# NinjaLantern-171001.net
KiCad netlist of a schematic drawn in EAGLE
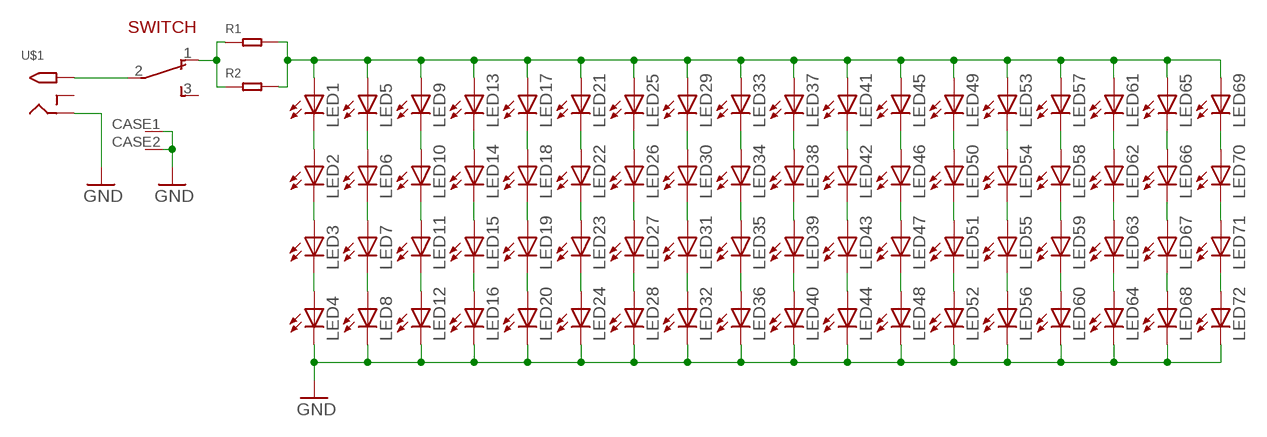
[diagram p0: schematic, sheet 1]

(export (version "E")
  (design (tool "Eeschema 10.0.6"))
  (components
    (comp (ref "LED1")
      (value "LED5MM")
      (footprint "eagle-import:LED5MM")
      (libsource (lib "eagle-import") (part "LED5MM"))
    )
    (comp (ref "LED2")
      (value "LED5MM")
      (footprint "eagle-import:LED5MM")
      (libsource (lib "eagle-import") (part "LED5MM"))
    )
    (comp (ref "LED3")
      (value "LED5MM")
      (footprint "eagle-import:LED5MM")
      (libsource (lib "eagle-import") (part "LED5MM"))
    )
    (comp (ref "LED4")
      (value "LED5MM")
      (footprint "eagle-import:LED5MM")
      (libsource (lib "eagle-import") (part "LED5MM"))
    )
    (comp (ref "LED5")
      (value "LED5MM")
      (footprint "eagle-import:LED5MM")
      (libsource (lib "eagle-import") (part "LED5MM"))
    )
    (comp (ref "LED6")
      (value "LED5MM")
      (footprint "eagle-import:LED5MM")
      (libsource (lib "eagle-import") (part "LED5MM"))
    )
    (comp (ref "LED7")
      (value "LED5MM")
      (footprint "eagle-import:LED5MM")
      (libsource (lib "eagle-import") (part "LED5MM"))
    )
    (comp (ref "LED8")
      (value "LED5MM")
      (footprint "eagle-import:LED5MM")
      (libsource (lib "eagle-import") (part "LED5MM"))
    )
    (comp (ref "LED9")
      (value "LED5MM")
      (footprint "eagle-import:LED5MM")
      (libsource (lib "eagle-import") (part "LED5MM"))
    )
    (comp (ref "LED10")
      (value "LED5MM")
      (footprint "eagle-import:LED5MM")
      (libsource (lib "eagle-import") (part "LED5MM"))
    )
    (comp (ref "LED11")
      (value "LED5MM")
      (footprint "eagle-import:LED5MM")
      (libsource (lib "eagle-import") (part "LED5MM"))
    )
    (comp (ref "LED12")
      (value "LED5MM")
      (footprint "eagle-import:LED5MM")
      (libsource (lib "eagle-import") (part "LED5MM"))
    )
    (comp (ref "LED13")
      (value "LED5MM")
      (footprint "eagle-import:LED5MM")
      (libsource (lib "eagle-import") (part "LED5MM"))
    )
    (comp (ref "LED14")
      (value "LED5MM")
      (footprint "eagle-import:LED5MM")
      (libsource (lib "eagle-import") (part "LED5MM"))
    )
    (comp (ref "LED15")
      (value "LED5MM")
      (footprint "eagle-import:LED5MM")
      (libsource (lib "eagle-import") (part "LED5MM"))
    )
    (comp (ref "LED16")
      (value "LED5MM")
      (footprint "eagle-import:LED5MM")
      (libsource (lib "eagle-import") (part "LED5MM"))
    )
    (comp (ref "LED17")
      (value "LED5MM")
      (footprint "eagle-import:LED5MM")
      (libsource (lib "eagle-import") (part "LED5MM"))
    )
    (comp (ref "LED18")
      (value "LED5MM")
      (footprint "eagle-import:LED5MM")
      (libsource (lib "eagle-import") (part "LED5MM"))
    )
    (comp (ref "LED19")
      (value "LED5MM")
      (footprint "eagle-import:LED5MM")
      (libsource (lib "eagle-import") (part "LED5MM"))
    )
    (comp (ref "LED20")
      (value "LED5MM")
      (footprint "eagle-import:LED5MM")
      (libsource (lib "eagle-import") (part "LED5MM"))
    )
    (comp (ref "LED21")
      (value "LED5MM")
      (footprint "eagle-import:LED5MM")
      (libsource (lib "eagle-import") (part "LED5MM"))
    )
    (comp (ref "LED22")
      (value "LED5MM")
      (footprint "eagle-import:LED5MM")
      (libsource (lib "eagle-import") (part "LED5MM"))
    )
    (comp (ref "LED23")
      (value "LED5MM")
      (footprint "eagle-import:LED5MM")
      (libsource (lib "eagle-import") (part "LED5MM"))
    )
    (comp (ref "LED24")
      (value "LED5MM")
      (footprint "eagle-import:LED5MM")
      (libsource (lib "eagle-import") (part "LED5MM"))
    )
    (comp (ref "LED25")
      (value "LED5MM")
      (footprint "eagle-import:LED5MM")
      (libsource (lib "eagle-import") (part "LED5MM"))
    )
    (comp (ref "LED26")
      (value "LED5MM")
      (footprint "eagle-import:LED5MM")
      (libsource (lib "eagle-import") (part "LED5MM"))
    )
    (comp (ref "LED27")
      (value "LED5MM")
      (footprint "eagle-import:LED5MM")
      (libsource (lib "eagle-import") (part "LED5MM"))
    )
    (comp (ref "LED28")
      (value "LED5MM")
      (footprint "eagle-import:LED5MM")
      (libsource (lib "eagle-import") (part "LED5MM"))
    )
    (comp (ref "LED29")
      (value "LED5MM")
      (footprint "eagle-import:LED5MM")
      (libsource (lib "eagle-import") (part "LED5MM"))
    )
    (comp (ref "LED30")
      (value "LED5MM")
      (footprint "eagle-import:LED5MM")
      (libsource (lib "eagle-import") (part "LED5MM"))
    )
    (comp (ref "LED31")
      (value "LED5MM")
      (footprint "eagle-import:LED5MM")
      (libsource (lib "eagle-import") (part "LED5MM"))
    )
    (comp (ref "LED32")
      (value "LED5MM")
      (footprint "eagle-import:LED5MM")
      (libsource (lib "eagle-import") (part "LED5MM"))
    )
    (comp (ref "LED33")
      (value "LED5MM")
      (footprint "eagle-import:LED5MM")
      (libsource (lib "eagle-import") (part "LED5MM"))
    )
    (comp (ref "LED34")
      (value "LED5MM")
      (footprint "eagle-import:LED5MM")
      (libsource (lib "eagle-import") (part "LED5MM"))
    )
    (comp (ref "LED35")
      (value "LED5MM")
      (footprint "eagle-import:LED5MM")
      (libsource (lib "eagle-import") (part "LED5MM"))
    )
    (comp (ref "LED36")
      (value "LED5MM")
      (footprint "eagle-import:LED5MM")
      (libsource (lib "eagle-import") (part "LED5MM"))
    )
    (comp (ref "LED37")
      (value "LED5MM")
      (footprint "eagle-import:LED5MM")
      (libsource (lib "eagle-import") (part "LED5MM"))
    )
    (comp (ref "LED38")
      (value "LED5MM")
      (footprint "eagle-import:LED5MM")
      (libsource (lib "eagle-import") (part "LED5MM"))
    )
    (comp (ref "LED39")
      (value "LED5MM")
      (footprint "eagle-import:LED5MM")
      (libsource (lib "eagle-import") (part "LED5MM"))
    )
    (comp (ref "LED40")
      (value "LED5MM")
      (footprint "eagle-import:LED5MM")
      (libsource (lib "eagle-import") (part "LED5MM"))
    )
    (comp (ref "LED41")
      (value "LED5MM")
      (footprint "eagle-import:LED5MM")
      (libsource (lib "eagle-import") (part "LED5MM"))
    )
    (comp (ref "LED42")
      (value "LED5MM")
      (footprint "eagle-import:LED5MM")
      (libsource (lib "eagle-import") (part "LED5MM"))
    )
    (comp (ref "LED43")
      (value "LED5MM")
      (footprint "eagle-import:LED5MM")
      (libsource (lib "eagle-import") (part "LED5MM"))
    )
    (comp (ref "LED44")
      (value "LED5MM")
      (footprint "eagle-import:LED5MM")
      (libsource (lib "eagle-import") (part "LED5MM"))
    )
    (comp (ref "LED45")
      (value "LED5MM")
      (footprint "eagle-import:LED5MM")
      (libsource (lib "eagle-import") (part "LED5MM"))
    )
    (comp (ref "LED46")
      (value "LED5MM")
      (footprint "eagle-import:LED5MM")
      (libsource (lib "eagle-import") (part "LED5MM"))
    )
    (comp (ref "LED47")
      (value "LED5MM")
      (footprint "eagle-import:LED5MM")
      (libsource (lib "eagle-import") (part "LED5MM"))
    )
    (comp (ref "LED48")
      (value "LED5MM")
      (footprint "eagle-import:LED5MM")
      (libsource (lib "eagle-import") (part "LED5MM"))
    )
    (comp (ref "LED49")
      (value "LED5MM")
      (footprint "eagle-import:LED5MM")
      (libsource (lib "eagle-import") (part "LED5MM"))
    )
    (comp (ref "LED50")
      (value "LED5MM")
      (footprint "eagle-import:LED5MM")
      (libsource (lib "eagle-import") (part "LED5MM"))
    )
    (comp (ref "LED51")
      (value "LED5MM")
      (footprint "eagle-import:LED5MM")
      (libsource (lib "eagle-import") (part "LED5MM"))
    )
    (comp (ref "LED52")
      (value "LED5MM")
      (footprint "eagle-import:LED5MM")
      (libsource (lib "eagle-import") (part "LED5MM"))
    )
    (comp (ref "LED53")
      (value "LED5MM")
      (footprint "eagle-import:LED5MM")
      (libsource (lib "eagle-import") (part "LED5MM"))
    )
    (comp (ref "LED54")
      (value "LED5MM")
      (footprint "eagle-import:LED5MM")
      (libsource (lib "eagle-import") (part "LED5MM"))
    )
    (comp (ref "LED55")
      (value "LED5MM")
      (footprint "eagle-import:LED5MM")
      (libsource (lib "eagle-import") (part "LED5MM"))
    )
    (comp (ref "LED56")
      (value "LED5MM")
      (footprint "eagle-import:LED5MM")
      (libsource (lib "eagle-import") (part "LED5MM"))
    )
    (comp (ref "LED57")
      (value "LED5MM")
      (footprint "eagle-import:LED5MM")
      (libsource (lib "eagle-import") (part "LED5MM"))
    )
    (comp (ref "LED58")
      (value "LED5MM")
      (footprint "eagle-import:LED5MM")
      (libsource (lib "eagle-import") (part "LED5MM"))
    )
    (comp (ref "LED59")
      (value "LED5MM")
      (footprint "eagle-import:LED5MM")
      (libsource (lib "eagle-import") (part "LED5MM"))
    )
    (comp (ref "LED60")
      (value "LED5MM")
      (footprint "eagle-import:LED5MM")
      (libsource (lib "eagle-import") (part "LED5MM"))
    )
    (comp (ref "LED61")
      (value "LED5MM")
      (footprint "eagle-import:LED5MM")
      (libsource (lib "eagle-import") (part "LED5MM"))
    )
    (comp (ref "LED62")
      (value "LED5MM")
      (footprint "eagle-import:LED5MM")
      (libsource (lib "eagle-import") (part "LED5MM"))
    )
    (comp (ref "LED63")
      (value "LED5MM")
      (footprint "eagle-import:LED5MM")
      (libsource (lib "eagle-import") (part "LED5MM"))
    )
    (comp (ref "LED64")
      (value "LED5MM")
      (footprint "eagle-import:LED5MM")
      (libsource (lib "eagle-import") (part "LED5MM"))
    )
    (comp (ref "LED65")
      (value "LED5MM")
      (footprint "eagle-import:LED5MM")
      (libsource (lib "eagle-import") (part "LED5MM"))
    )
    (comp (ref "LED66")
      (value "LED5MM")
      (footprint "eagle-import:LED5MM")
      (libsource (lib "eagle-import") (part "LED5MM"))
    )
    (comp (ref "LED67")
      (value "LED5MM")
      (footprint "eagle-import:LED5MM")
      (libsource (lib "eagle-import") (part "LED5MM"))
    )
    (comp (ref "LED68")
      (value "LED5MM")
      (footprint "eagle-import:LED5MM")
      (libsource (lib "eagle-import") (part "LED5MM"))
    )
    (comp (ref "LED69")
      (value "LED5MM")
      (footprint "eagle-import:LED5MM")
      (libsource (lib "eagle-import") (part "LED5MM"))
    )
    (comp (ref "LED70")
      (value "LED5MM")
      (footprint "eagle-import:LED5MM")
      (libsource (lib "eagle-import") (part "LED5MM"))
    )
    (comp (ref "LED71")
      (value "LED5MM")
      (footprint "eagle-import:LED5MM")
      (libsource (lib "eagle-import") (part "LED5MM"))
    )
    (comp (ref "LED72")
      (value "LED5MM")
      (footprint "eagle-import:LED5MM")
      (libsource (lib "eagle-import") (part "LED5MM"))
    )
    (comp (ref "R1")
      (value "DIP-RES-100R-5%-1/4W(PR-D2.3XL6.5MM)")
      (footprint "eagle-import:PR-D2.3XL6.5MM")
      (fields (field (name "MPN") "FHCFR-1/4W-101J"))
      (libsource (lib "eagle-import") (part "DIP-RES-100R-5%-1/4W(PR-D2.3XL6.5MM)"))
    )
    (comp (ref "R2")
      (value "DIP-RES-100R-5%-1/4W(PR-D2.3XL6.5MM)")
      (footprint "eagle-import:PR-D2.3XL6.5MM")
      (fields (field (name "MPN") "FHCFR-1/4W-101J"))
      (libsource (lib "eagle-import") (part "DIP-RES-100R-5%-1/4W(PR-D2.3XL6.5MM)"))
    )
    (comp (ref "SWITCH")
      (value "4MS1R202M6QES")
      (footprint "eagle-import:4MS1R202M6QES")
      (libsource (lib "eagle-import") (part "4MS1R202M6QES"))
    )
    (comp (ref "U$1")
      (value "2.1MMJACKTHM")
      (footprint "eagle-import:PJ-102A")
      (libsource (lib "eagle-import") (part "2.1MMJACKTHM"))
    )
  )
  (nets
    (net (code "1") (name "GND") (class "Default")
      (node (ref "LED12") (pin "K") (pinfunction "C_K") (pintype "passive"))
      (node (ref "LED16") (pin "K") (pinfunction "C_K") (pintype "passive"))
      (node (ref "LED20") (pin "K") (pinfunction "C_K") (pintype "passive"))
      (node (ref "LED24") (pin "K") (pinfunction "C_K") (pintype "passive"))
      (node (ref "LED28") (pin "K") (pinfunction "C_K") (pintype "passive"))
      (node (ref "LED32") (pin "K") (pinfunction "C_K") (pintype "passive"))
      (node (ref "LED36") (pin "K") (pinfunction "C_K") (pintype "passive"))
      (node (ref "LED4") (pin "K") (pinfunction "C_K") (pintype "passive"))
      (node (ref "LED40") (pin "K") (pinfunction "C_K") (pintype "passive"))
      (node (ref "LED44") (pin "K") (pinfunction "C_K") (pintype "passive"))
      (node (ref "LED48") (pin "K") (pinfunction "C_K") (pintype "passive"))
      (node (ref "LED52") (pin "K") (pinfunction "C_K") (pintype "passive"))
      (node (ref "LED56") (pin "K") (pinfunction "C_K") (pintype "passive"))
      (node (ref "LED60") (pin "K") (pinfunction "C_K") (pintype "passive"))
      (node (ref "LED64") (pin "K") (pinfunction "C_K") (pintype "passive"))
      (node (ref "LED68") (pin "K") (pinfunction "C_K") (pintype "passive"))
      (node (ref "LED72") (pin "K") (pinfunction "C_K") (pintype "passive"))
      (node (ref "LED8") (pin "K") (pinfunction "C_K") (pintype "passive"))
      (node (ref "U$1") (pin "RING") (pinfunction "RING_RING") (pintype "bidirectional"))
    )
    (net (code "2") (name "Net-(LED1-C)") (class "Default")
      (node (ref "LED1") (pin "K") (pinfunction "C_K") (pintype "passive"))
      (node (ref "LED2") (pin "A") (pinfunction "A_A") (pintype "passive"))
    )
    (net (code "3") (name "Net-(LED1-PadA)") (class "Default")
      (node (ref "LED1") (pin "A") (pinfunction "A_A") (pintype "passive"))
      (node (ref "LED13") (pin "A") (pinfunction "A_A") (pintype "passive"))
      (node (ref "LED17") (pin "A") (pinfunction "A_A") (pintype "passive"))
      (node (ref "LED21") (pin "A") (pinfunction "A_A") (pintype "passive"))
      (node (ref "LED25") (pin "A") (pinfunction "A_A") (pintype "passive"))
      (node (ref "LED29") (pin "A") (pinfunction "A_A") (pintype "passive"))
      (node (ref "LED33") (pin "A") (pinfunction "A_A") (pintype "passive"))
      (node (ref "LED37") (pin "A") (pinfunction "A_A") (pintype "passive"))
      (node (ref "LED41") (pin "A") (pinfunction "A_A") (pintype "passive"))
      (node (ref "LED45") (pin "A") (pinfunction "A_A") (pintype "passive"))
      (node (ref "LED49") (pin "A") (pinfunction "A_A") (pintype "passive"))
      (node (ref "LED5") (pin "A") (pinfunction "A_A") (pintype "passive"))
      (node (ref "LED53") (pin "A") (pinfunction "A_A") (pintype "passive"))
      (node (ref "LED57") (pin "A") (pinfunction "A_A") (pintype "passive"))
      (node (ref "LED61") (pin "A") (pinfunction "A_A") (pintype "passive"))
      (node (ref "LED65") (pin "A") (pinfunction "A_A") (pintype "passive"))
      (node (ref "LED69") (pin "A") (pinfunction "A_A") (pintype "passive"))
      (node (ref "LED9") (pin "A") (pinfunction "A_A") (pintype "passive"))
      (node (ref "R1") (pin "2") (pinfunction "2_2") (pintype "passive"))
      (node (ref "R2") (pin "2") (pinfunction "2_2") (pintype "passive"))
    )
    (net (code "4") (name "Net-(LED2-C)") (class "Default")
      (node (ref "LED2") (pin "K") (pinfunction "C_K") (pintype "passive"))
      (node (ref "LED3") (pin "A") (pinfunction "A_A") (pintype "passive"))
    )
    (net (code "5") (name "Net-(LED3-C)") (class "Default")
      (node (ref "LED3") (pin "K") (pinfunction "C_K") (pintype "passive"))
      (node (ref "LED4") (pin "A") (pinfunction "A_A") (pintype "passive"))
    )
    (net (code "6") (name "Net-(LED5-C)") (class "Default")
      (node (ref "LED5") (pin "K") (pinfunction "C_K") (pintype "passive"))
      (node (ref "LED6") (pin "A") (pinfunction "A_A") (pintype "passive"))
    )
    (net (code "7") (name "Net-(LED6-C)") (class "Default")
      (node (ref "LED6") (pin "K") (pinfunction "C_K") (pintype "passive"))
      (node (ref "LED7") (pin "A") (pinfunction "A_A") (pintype "passive"))
    )
    (net (code "8") (name "Net-(LED7-C)") (class "Default")
      (node (ref "LED7") (pin "K") (pinfunction "C_K") (pintype "passive"))
      (node (ref "LED8") (pin "A") (pinfunction "A_A") (pintype "passive"))
    )
    (net (code "9") (name "Net-(LED9-C)") (class "Default")
      (node (ref "LED10") (pin "A") (pinfunction "A_A") (pintype "passive"))
      (node (ref "LED9") (pin "K") (pinfunction "C_K") (pintype "passive"))
    )
    (net (code "10") (name "Net-(LED10-C)") (class "Default")
      (node (ref "LED10") (pin "K") (pinfunction "C_K") (pintype "passive"))
      (node (ref "LED11") (pin "A") (pinfunction "A_A") (pintype "passive"))
    )
    (net (code "11") (name "Net-(LED11-C)") (class "Default")
      (node (ref "LED11") (pin "K") (pinfunction "C_K") (pintype "passive"))
      (node (ref "LED12") (pin "A") (pinfunction "A_A") (pintype "passive"))
    )
    (net (code "12") (name "Net-(LED13-C)") (class "Default")
      (node (ref "LED13") (pin "K") (pinfunction "C_K") (pintype "passive"))
      (node (ref "LED14") (pin "A") (pinfunction "A_A") (pintype "passive"))
    )
    (net (code "13") (name "Net-(LED14-C)") (class "Default")
      (node (ref "LED14") (pin "K") (pinfunction "C_K") (pintype "passive"))
      (node (ref "LED15") (pin "A") (pinfunction "A_A") (pintype "passive"))
    )
    (net (code "14") (name "Net-(LED15-C)") (class "Default")
      (node (ref "LED15") (pin "K") (pinfunction "C_K") (pintype "passive"))
      (node (ref "LED16") (pin "A") (pinfunction "A_A") (pintype "passive"))
    )
    (net (code "15") (name "Net-(LED17-C)") (class "Default")
      (node (ref "LED17") (pin "K") (pinfunction "C_K") (pintype "passive"))
      (node (ref "LED18") (pin "A") (pinfunction "A_A") (pintype "passive"))
    )
    (net (code "16") (name "Net-(LED18-C)") (class "Default")
      (node (ref "LED18") (pin "K") (pinfunction "C_K") (pintype "passive"))
      (node (ref "LED19") (pin "A") (pinfunction "A_A") (pintype "passive"))
    )
    (net (code "17") (name "Net-(LED19-C)") (class "Default")
      (node (ref "LED19") (pin "K") (pinfunction "C_K") (pintype "passive"))
      (node (ref "LED20") (pin "A") (pinfunction "A_A") (pintype "passive"))
    )
    (net (code "18") (name "Net-(LED21-C)") (class "Default")
      (node (ref "LED21") (pin "K") (pinfunction "C_K") (pintype "passive"))
      (node (ref "LED22") (pin "A") (pinfunction "A_A") (pintype "passive"))
    )
    (net (code "19") (name "Net-(LED22-C)") (class "Default")
      (node (ref "LED22") (pin "K") (pinfunction "C_K") (pintype "passive"))
      (node (ref "LED23") (pin "A") (pinfunction "A_A") (pintype "passive"))
    )
    (net (code "20") (name "Net-(LED23-C)") (class "Default")
      (node (ref "LED23") (pin "K") (pinfunction "C_K") (pintype "passive"))
      (node (ref "LED24") (pin "A") (pinfunction "A_A") (pintype "passive"))
    )
    (net (code "21") (name "Net-(LED25-C)") (class "Default")
      (node (ref "LED25") (pin "K") (pinfunction "C_K") (pintype "passive"))
      (node (ref "LED26") (pin "A") (pinfunction "A_A") (pintype "passive"))
    )
    (net (code "22") (name "Net-(LED26-C)") (class "Default")
      (node (ref "LED26") (pin "K") (pinfunction "C_K") (pintype "passive"))
      (node (ref "LED27") (pin "A") (pinfunction "A_A") (pintype "passive"))
    )
    (net (code "23") (name "Net-(LED27-C)") (class "Default")
      (node (ref "LED27") (pin "K") (pinfunction "C_K") (pintype "passive"))
      (node (ref "LED28") (pin "A") (pinfunction "A_A") (pintype "passive"))
    )
    (net (code "24") (name "Net-(LED29-C)") (class "Default")
      (node (ref "LED29") (pin "K") (pinfunction "C_K") (pintype "passive"))
      (node (ref "LED30") (pin "A") (pinfunction "A_A") (pintype "passive"))
    )
    (net (code "25") (name "Net-(LED30-C)") (class "Default")
      (node (ref "LED30") (pin "K") (pinfunction "C_K") (pintype "passive"))
      (node (ref "LED31") (pin "A") (pinfunction "A_A") (pintype "passive"))
    )
    (net (code "26") (name "Net-(LED31-C)") (class "Default")
      (node (ref "LED31") (pin "K") (pinfunction "C_K") (pintype "passive"))
      (node (ref "LED32") (pin "A") (pinfunction "A_A") (pintype "passive"))
    )
    (net (code "27") (name "Net-(LED33-C)") (class "Default")
      (node (ref "LED33") (pin "K") (pinfunction "C_K") (pintype "passive"))
      (node (ref "LED34") (pin "A") (pinfunction "A_A") (pintype "passive"))
    )
    (net (code "28") (name "Net-(LED34-C)") (class "Default")
      (node (ref "LED34") (pin "K") (pinfunction "C_K") (pintype "passive"))
      (node (ref "LED35") (pin "A") (pinfunction "A_A") (pintype "passive"))
    )
    (net (code "29") (name "Net-(LED35-C)") (class "Default")
      (node (ref "LED35") (pin "K") (pinfunction "C_K") (pintype "passive"))
      (node (ref "LED36") (pin "A") (pinfunction "A_A") (pintype "passive"))
    )
    (net (code "30") (name "Net-(LED37-C)") (class "Default")
      (node (ref "LED37") (pin "K") (pinfunction "C_K") (pintype "passive"))
      (node (ref "LED38") (pin "A") (pinfunction "A_A") (pintype "passive"))
    )
    (net (code "31") (name "Net-(LED38-C)") (class "Default")
      (node (ref "LED38") (pin "K") (pinfunction "C_K") (pintype "passive"))
      (node (ref "LED39") (pin "A") (pinfunction "A_A") (pintype "passive"))
    )
    (net (code "32") (name "Net-(LED39-C)") (class "Default")
      (node (ref "LED39") (pin "K") (pinfunction "C_K") (pintype "passive"))
      (node (ref "LED40") (pin "A") (pinfunction "A_A") (pintype "passive"))
    )
    (net (code "33") (name "Net-(LED41-C)") (class "Default")
      (node (ref "LED41") (pin "K") (pinfunction "C_K") (pintype "passive"))
      (node (ref "LED42") (pin "A") (pinfunction "A_A") (pintype "passive"))
    )
    (net (code "34") (name "Net-(LED42-C)") (class "Default")
      (node (ref "LED42") (pin "K") (pinfunction "C_K") (pintype "passive"))
      (node (ref "LED43") (pin "A") (pinfunction "A_A") (pintype "passive"))
    )
    (net (code "35") (name "Net-(LED43-C)") (class "Default")
      (node (ref "LED43") (pin "K") (pinfunction "C_K") (pintype "passive"))
      (node (ref "LED44") (pin "A") (pinfunction "A_A") (pintype "passive"))
    )
    (net (code "36") (name "Net-(LED45-C)") (class "Default")
      (node (ref "LED45") (pin "K") (pinfunction "C_K") (pintype "passive"))
      (node (ref "LED46") (pin "A") (pinfunction "A_A") (pintype "passive"))
    )
    (net (code "37") (name "Net-(LED46-C)") (class "Default")
      (node (ref "LED46") (pin "K") (pinfunction "C_K") (pintype "passive"))
      (node (ref "LED47") (pin "A") (pinfunction "A_A") (pintype "passive"))
    )
    (net (code "38") (name "Net-(LED47-C)") (class "Default")
      (node (ref "LED47") (pin "K") (pinfunction "C_K") (pintype "passive"))
      (node (ref "LED48") (pin "A") (pinfunction "A_A") (pintype "passive"))
    )
    (net (code "39") (name "Net-(LED49-C)") (class "Default")
      (node (ref "LED49") (pin "K") (pinfunction "C_K") (pintype "passive"))
      (node (ref "LED50") (pin "A") (pinfunction "A_A") (pintype "passive"))
    )
    (net (code "40") (name "Net-(LED50-C)") (class "Default")
      (node (ref "LED50") (pin "K") (pinfunction "C_K") (pintype "passive"))
      (node (ref "LED51") (pin "A") (pinfunction "A_A") (pintype "passive"))
    )
    (net (code "41") (name "Net-(LED51-C)") (class "Default")
      (node (ref "LED51") (pin "K") (pinfunction "C_K") (pintype "passive"))
      (node (ref "LED52") (pin "A") (pinfunction "A_A") (pintype "passive"))
    )
    (net (code "42") (name "Net-(LED53-C)") (class "Default")
      (node (ref "LED53") (pin "K") (pinfunction "C_K") (pintype "passive"))
      (node (ref "LED54") (pin "A") (pinfunction "A_A") (pintype "passive"))
    )
    (net (code "43") (name "Net-(LED54-C)") (class "Default")
      (node (ref "LED54") (pin "K") (pinfunction "C_K") (pintype "passive"))
      (node (ref "LED55") (pin "A") (pinfunction "A_A") (pintype "passive"))
    )
    (net (code "44") (name "Net-(LED55-C)") (class "Default")
      (node (ref "LED55") (pin "K") (pinfunction "C_K") (pintype "passive"))
      (node (ref "LED56") (pin "A") (pinfunction "A_A") (pintype "passive"))
    )
    (net (code "45") (name "Net-(LED57-C)") (class "Default")
      (node (ref "LED57") (pin "K") (pinfunction "C_K") (pintype "passive"))
      (node (ref "LED58") (pin "A") (pinfunction "A_A") (pintype "passive"))
    )
    (net (code "46") (name "Net-(LED58-C)") (class "Default")
      (node (ref "LED58") (pin "K") (pinfunction "C_K") (pintype "passive"))
      (node (ref "LED59") (pin "A") (pinfunction "A_A") (pintype "passive"))
    )
    (net (code "47") (name "Net-(LED59-C)") (class "Default")
      (node (ref "LED59") (pin "K") (pinfunction "C_K") (pintype "passive"))
      (node (ref "LED60") (pin "A") (pinfunction "A_A") (pintype "passive"))
    )
    (net (code "48") (name "Net-(LED61-C)") (class "Default")
      (node (ref "LED61") (pin "K") (pinfunction "C_K") (pintype "passive"))
      (node (ref "LED62") (pin "A") (pinfunction "A_A") (pintype "passive"))
    )
    (net (code "49") (name "Net-(LED62-C)") (class "Default")
      (node (ref "LED62") (pin "K") (pinfunction "C_K") (pintype "passive"))
      (node (ref "LED63") (pin "A") (pinfunction "A_A") (pintype "passive"))
    )
    (net (code "50") (name "Net-(LED63-C)") (class "Default")
      (node (ref "LED63") (pin "K") (pinfunction "C_K") (pintype "passive"))
      (node (ref "LED64") (pin "A") (pinfunction "A_A") (pintype "passive"))
    )
    (net (code "51") (name "Net-(LED65-C)") (class "Default")
      (node (ref "LED65") (pin "K") (pinfunction "C_K") (pintype "passive"))
      (node (ref "LED66") (pin "A") (pinfunction "A_A") (pintype "passive"))
    )
    (net (code "52") (name "Net-(LED66-C)") (class "Default")
      (node (ref "LED66") (pin "K") (pinfunction "C_K") (pintype "passive"))
      (node (ref "LED67") (pin "A") (pinfunction "A_A") (pintype "passive"))
    )
    (net (code "53") (name "Net-(LED67-C)") (class "Default")
      (node (ref "LED67") (pin "K") (pinfunction "C_K") (pintype "passive"))
      (node (ref "LED68") (pin "A") (pinfunction "A_A") (pintype "passive"))
    )
    (net (code "54") (name "Net-(LED69-C)") (class "Default")
      (node (ref "LED69") (pin "K") (pinfunction "C_K") (pintype "passive"))
      (node (ref "LED70") (pin "A") (pinfunction "A_A") (pintype "passive"))
    )
    (net (code "55") (name "Net-(LED70-C)") (class "Default")
      (node (ref "LED70") (pin "K") (pinfunction "C_K") (pintype "passive"))
      (node (ref "LED71") (pin "A") (pinfunction "A_A") (pintype "passive"))
    )
    (net (code "56") (name "Net-(LED71-C)") (class "Default")
      (node (ref "LED71") (pin "K") (pinfunction "C_K") (pintype "passive"))
      (node (ref "LED72") (pin "A") (pinfunction "A_A") (pintype "passive"))
    )
    (net (code "57") (name "Net-(R1-Pad1)") (class "Default")
      (node (ref "R1") (pin "1") (pinfunction "1_1") (pintype "passive"))
      (node (ref "R2") (pin "1") (pinfunction "1_1") (pintype "passive"))
      (node (ref "SWITCH") (pin "1") (pinfunction "1_1") (pintype "passive"))
    )
    (net (code "58") (name "Net-(SWITCH-Pad2)") (class "Default")
      (node (ref "SWITCH") (pin "2") (pinfunction "2_2") (pintype "passive"))
      (node (ref "U$1") (pin "TIP") (pinfunction "TIP_TIP") (pintype "bidirectional"))
    )
    (net (code "59") (name "unconnected-(SWITCH-Pad3)") (class "Default")
      (node (ref "SWITCH") (pin "3") (pinfunction "3_3") (pintype "passive"))
    )
    (net (code "60") (name "unconnected-(SWITCH-PadCASE1)") (class "Default")
      (node (ref "SWITCH") (pin "CASE1") (pinfunction "CASE1_CASE1") (pintype "passive"))
    )
    (net (code "61") (name "unconnected-(SWITCH-PadCASE2)") (class "Default")
      (node (ref "SWITCH") (pin "CASE2") (pinfunction "CASE2_CASE2") (pintype "passive"))
    )
    (net (code "62") (name "unconnected-(U$1-PadRING_SW)") (class "Default")
      (node (ref "U$1") (pin "RING_SW") (pinfunction "RING_SW_RING_SW") (pintype "bidirectional"))
    )
  )
)
